# DMXController.net
KiCad netlist of a schematic drawn in Altium Designer
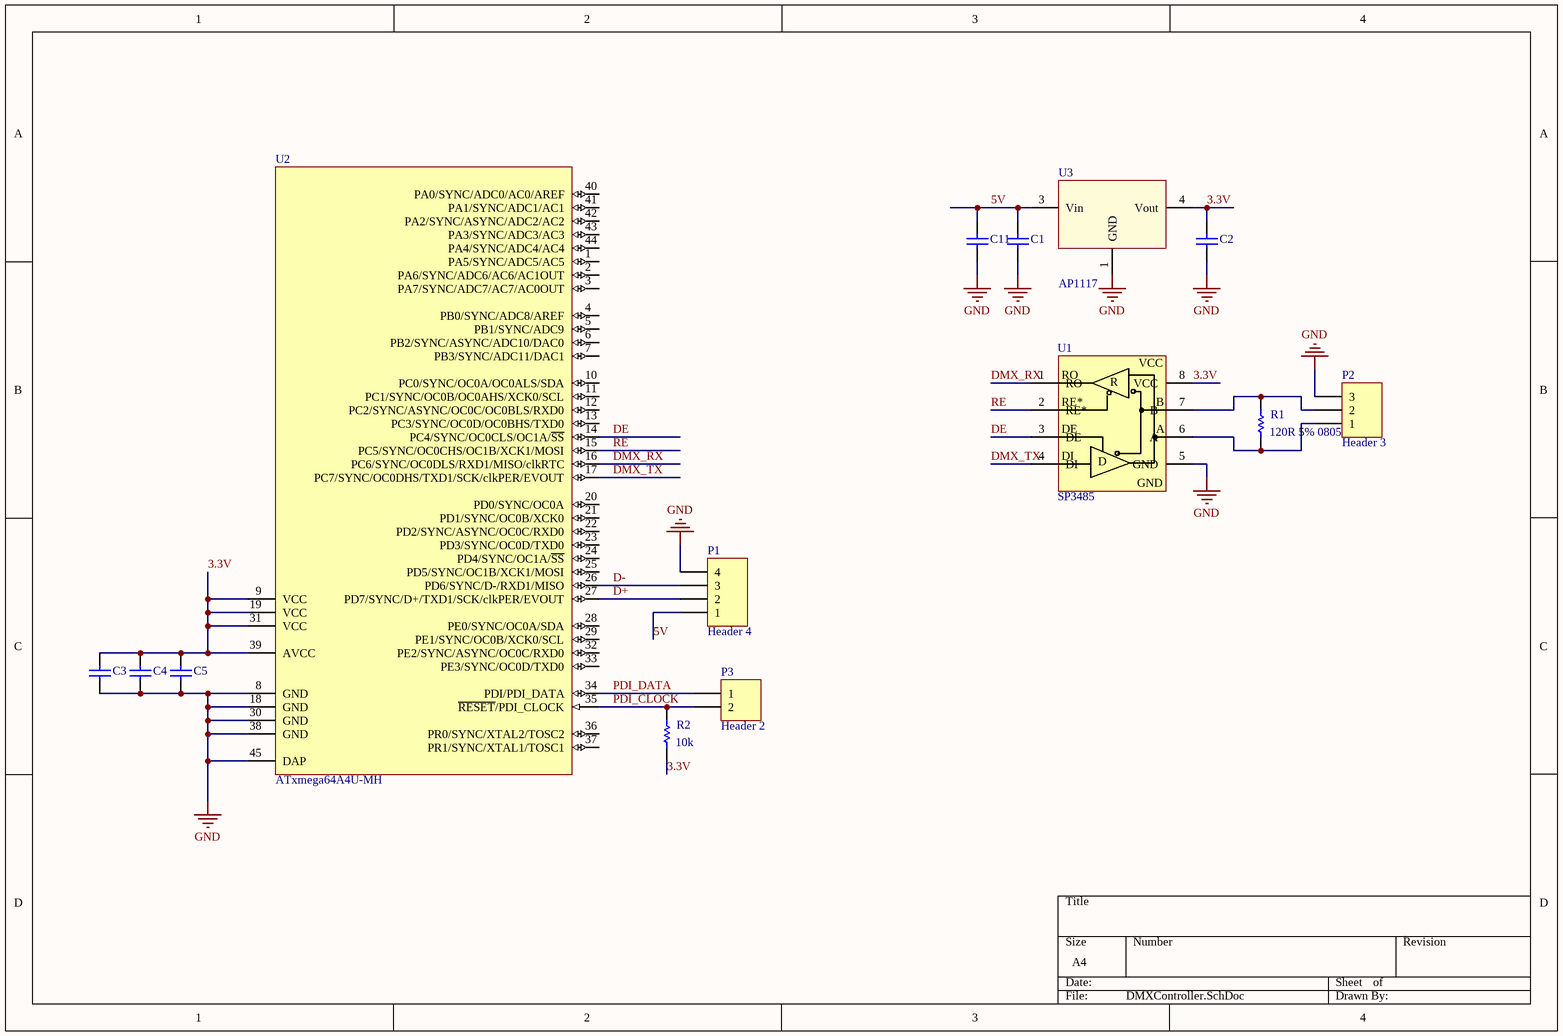
[diagram p0: DMXController.SchDoc]

(export (version "E")
  (design (tool "Eeschema 10.0.6"))
  (components
    (comp (ref "C1")
      (value "10u")
      (footprint "CAPC0805(2012)100_M")
      (description "CAP 1uF 10V ±10% 0805 (2012 Metric) Thickness 1mm SMD")
      (fields (field (name "TOLERANCE") "±10%"))
      (libsource (lib "Altium Content Vault") (part "CMP-1036-04739-1"))
    )
    (comp (ref "C2")
      (value "22u")
      (footprint "CAPC0805(2012)100_M")
      (description "CAP 1uF 10V ±10% 0805 (2012 Metric) Thickness 1mm SMD")
      (fields (field (name "TOLERANCE") "±10%"))
      (libsource (lib "Altium Content Vault") (part "CMP-1036-04739-1"))
    )
    (comp (ref "C3")
      (value "100n")
      (footprint "CAPC0805(2012)100_M")
      (description "CAP 1uF 10V ±10% 0805 (2012 Metric) Thickness 1mm SMD")
      (fields (field (name "TOLERANCE") "±10%"))
      (libsource (lib "Altium Content Vault") (part "CMP-1036-04739-1"))
    )
    (comp (ref "C4")
      (value "100n")
      (footprint "CAPC0805(2012)100_M")
      (description "CAP 1uF 10V ±10% 0805 (2012 Metric) Thickness 1mm SMD")
      (fields (field (name "TOLERANCE") "±10%"))
      (libsource (lib "Altium Content Vault") (part "CMP-1036-04739-1"))
    )
    (comp (ref "C5")
      (value "100n")
      (footprint "CAPC0805(2012)100_M")
      (description "CAP 1uF 10V ±10% 0805 (2012 Metric) Thickness 1mm SMD")
      (fields (field (name "TOLERANCE") "±10%"))
      (libsource (lib "Altium Content Vault") (part "CMP-1036-04739-1"))
    )
    (comp (ref "C11")
      (value "10u")
      (footprint "CAPC0805(2012)100_M")
      (description "CAP 1uF 10V ±10% 0805 (2012 Metric) Thickness 1mm SMD")
      (fields (field (name "TOLERANCE") "±10%"))
      (libsource (lib "Altium Content Vault") (part "CMP-1036-04739-1"))
    )
    (comp (ref "P1")
      (value "Header 4")
      (footprint "HDR1X4")
      (description "Header, 4-Pin")
      (fields (field (name "PUBLISHER") "Altium Limited"))
      (libsource (lib "Miscellaneous Connectors") (part "Header 4"))
    )
    (comp (ref "P2")
      (value "Header 3")
      (footprint "HDR1X3")
      (description "Header, 3-Pin")
      (fields (field (name "PUBLISHER") "Altium Limited"))
      (libsource (lib "Miscellaneous Connectors") (part "Header 3"))
    )
    (comp (ref "P3")
      (value "Header 2")
      (footprint "HDR1X2")
      (description "Header, 2-Pin")
      (fields (field (name "PUBLISHER") "Altium Limited"))
      (libsource (lib "Miscellaneous Connectors") (part "Header 2"))
    )
    (comp (ref "R1")
      (value "120R 5% 0805(2012)")
      (footprint "RESC0805(2012)_N")
      (description "120R 0.125W 5% 0805 (2012 Metric)  SMD")
      (fields (field (name "TOLERANCE") "5 %") (field (name "POWER") "0.125 W"))
      (libsource (lib "Altium Content Vault") (part "RES"))
    )
    (comp (ref "R2")
      (value "10k")
      (footprint "RESC0805(2012)_N")
      (description "120R 0.125W 5% 0805 (2012 Metric)  SMD")
      (fields (field (name "TOLERANCE") "5 %") (field (name "POWER") "0.125 W"))
      (libsource (lib "Altium Content Vault") (part "CMP-1013-00052-1"))
    )
    (comp (ref "U1") (value "SP3485") (footprint "SOIC8") (libsource (lib "Schlib1") (part "SP3485")))
    (comp (ref "U2")
      (value "ATxmega64A4U-MH")
      (footprint "44M1_L")
      (libsource (lib "Altium Content Vault") (part "MC-8B-ATXM16A4U-SQ45"))
    )
    (comp (ref "U3") (value "AP1117") (footprint "SOT-223") (libsource (lib "Schlib1") (part "AP1117")))
  )
  (nets
    (net (code "1") (name "/3.3V") (class "Default")
      (node (ref "C2") (pin "2") (pinfunction "2_2") (pintype "passive"))
      (node (ref "C3") (pin "2") (pinfunction "2_2") (pintype "passive"))
      (node (ref "C4") (pin "2") (pinfunction "2_2") (pintype "passive"))
      (node (ref "C5") (pin "2") (pinfunction "2_2") (pintype "passive"))
      (node (ref "R2") (pin "1") (pinfunction "1_1") (pintype "passive"))
      (node (ref "U1") (pin "8") (pinfunction "VCC_8") (pintype "passive"))
      (node (ref "U2") (pin "19") (pinfunction "VCC_19") (pintype "power_in"))
      (node (ref "U2") (pin "31") (pinfunction "VCC_31") (pintype "power_in"))
      (node (ref "U2") (pin "39") (pinfunction "AVCC_39") (pintype "power_in"))
      (node (ref "U2") (pin "9") (pinfunction "VCC_9") (pintype "power_in"))
      (node (ref "U3") (pin "4") (pinfunction "Vout_4") (pintype "passive"))
    )
    (net (code "2") (name "/5V") (class "Default")
      (node (ref "C1") (pin "2") (pinfunction "2_2") (pintype "passive"))
      (node (ref "C11") (pin "2") (pinfunction "2_2") (pintype "passive"))
      (node (ref "P1") (pin "1") (pinfunction "1_1") (pintype "passive"))
      (node (ref "U3") (pin "3") (pinfunction "Vin_3") (pintype "passive"))
    )
    (net (code "3") (name "/D+") (class "Default")
      (node (ref "P1") (pin "2") (pinfunction "2_2") (pintype "passive"))
      (node (ref "U2") (pin "27") (pinfunction "PD7/SYNC/D+/TXD1/SCK/clkPER/EVOUT_27") (pintype "bidirectional"))
    )
    (net (code "4") (name "/D-") (class "Default")
      (node (ref "P1") (pin "3") (pinfunction "3_3") (pintype "passive"))
      (node (ref "U2") (pin "26") (pinfunction "PD6/SYNC/D-/RXD1/MISO_26") (pintype "bidirectional"))
    )
    (net (code "5") (name "/DE") (class "Default")
      (node (ref "U1") (pin "3") (pinfunction "DE_3") (pintype "passive"))
      (node (ref "U2") (pin "14") (pinfunction "PC4/SYNC/OC0CLS/OC1A/~{SS}_14") (pintype "bidirectional"))
    )
    (net (code "6") (name "/DMX_RX") (class "Default")
      (node (ref "U1") (pin "1") (pinfunction "RO_1") (pintype "passive"))
      (node (ref "U2") (pin "16") (pinfunction "PC6/SYNC/OC0DLS/RXD1/MISO/clkRTC_16") (pintype "bidirectional"))
    )
    (net (code "7") (name "/DMX_TX") (class "Default")
      (node (ref "U1") (pin "4") (pinfunction "DI_4") (pintype "passive"))
      (node (ref "U2") (pin "17") (pinfunction "PC7/SYNC/OC0DHS/TXD1/SCK/clkPER/EVOUT_17") (pintype "bidirectional"))
    )
    (net (code "8") (name "/PDI_CLOCK") (class "Default")
      (node (ref "P3") (pin "2") (pinfunction "2_2") (pintype "passive"))
      (node (ref "R2") (pin "2") (pinfunction "2_2") (pintype "passive"))
      (node (ref "U2") (pin "35") (pinfunction "~{RESET}/PDI_CLOCK_35") (pintype "input"))
    )
    (net (code "9") (name "/PDI_DATA") (class "Default")
      (node (ref "P3") (pin "1") (pinfunction "1_1") (pintype "passive"))
      (node (ref "U2") (pin "34") (pinfunction "PDI/PDI_DATA_34") (pintype "bidirectional"))
    )
    (net (code "10") (name "/RE") (class "Default")
      (node (ref "U1") (pin "2") (pinfunction "RE*_2") (pintype "passive"))
      (node (ref "U2") (pin "15") (pinfunction "PC5/SYNC/OC0CHS/OC1B/XCK1/MOSI_15") (pintype "bidirectional"))
    )
    (net (code "11") (name "GND") (class "Default")
      (node (ref "C1") (pin "1") (pinfunction "1_1") (pintype "passive"))
      (node (ref "C11") (pin "1") (pinfunction "1_1") (pintype "passive"))
      (node (ref "C2") (pin "1") (pinfunction "1_1") (pintype "passive"))
      (node (ref "C3") (pin "1") (pinfunction "1_1") (pintype "passive"))
      (node (ref "C4") (pin "1") (pinfunction "1_1") (pintype "passive"))
      (node (ref "C5") (pin "1") (pinfunction "1_1") (pintype "passive"))
      (node (ref "P1") (pin "4") (pinfunction "4_4") (pintype "passive"))
      (node (ref "P2") (pin "3") (pinfunction "3_3") (pintype "passive"))
      (node (ref "U1") (pin "5") (pinfunction "GND_5") (pintype "passive"))
      (node (ref "U2") (pin "18") (pinfunction "GND_18") (pintype "power_in"))
      (node (ref "U2") (pin "30") (pinfunction "GND_30") (pintype "power_in"))
      (node (ref "U2") (pin "38") (pinfunction "GND_38") (pintype "power_in"))
      (node (ref "U2") (pin "45") (pinfunction "DAP_45") (pintype "power_in"))
      (node (ref "U2") (pin "8") (pinfunction "GND_8") (pintype "power_in"))
      (node (ref "U3") (pin "1") (pinfunction "GND_1") (pintype "passive"))
    )
    (net (code "12") (name "Net-(U1-A)") (class "Default")
      (node (ref "P2") (pin "1") (pinfunction "1_1") (pintype "passive"))
      (node (ref "R1") (pin "1") (pinfunction "1_1") (pintype "passive"))
      (node (ref "U1") (pin "6") (pinfunction "A_6") (pintype "passive"))
    )
    (net (code "13") (name "Net-(U1-B)") (class "Default")
      (node (ref "P2") (pin "2") (pinfunction "2_2") (pintype "passive"))
      (node (ref "R1") (pin "2") (pinfunction "2_2") (pintype "passive"))
      (node (ref "U1") (pin "7") (pinfunction "B_7") (pintype "passive"))
    )
    (net (code "14") (name "unconnected-(U2-PA0{slash}SYNC{slash}ADC0{slash}AC0{slash}AREF-Pad40)") (class "Default")
      (node (ref "U2") (pin "40") (pinfunction "PA0/SYNC/ADC0/AC0/AREF_40") (pintype "bidirectional"))
    )
    (net (code "15") (name "unconnected-(U2-PA1{slash}SYNC{slash}ADC1{slash}AC1-Pad41)") (class "Default")
      (node (ref "U2") (pin "41") (pinfunction "PA1/SYNC/ADC1/AC1_41") (pintype "bidirectional"))
    )
    (net (code "16") (name "unconnected-(U2-PA2{slash}SYNC{slash}ASYNC{slash}ADC2{slash}AC2-Pad42)") (class "Default")
      (node (ref "U2") (pin "42") (pinfunction "PA2/SYNC/ASYNC/ADC2/AC2_42") (pintype "bidirectional"))
    )
    (net (code "17") (name "unconnected-(U2-PA3{slash}SYNC{slash}ADC3{slash}AC3-Pad43)") (class "Default")
      (node (ref "U2") (pin "43") (pinfunction "PA3/SYNC/ADC3/AC3_43") (pintype "bidirectional"))
    )
    (net (code "18") (name "unconnected-(U2-PA4{slash}SYNC{slash}ADC4{slash}AC4-Pad44)") (class "Default")
      (node (ref "U2") (pin "44") (pinfunction "PA4/SYNC/ADC4/AC4_44") (pintype "bidirectional"))
    )
    (net (code "19") (name "unconnected-(U2-PA5{slash}SYNC{slash}ADC5{slash}AC5-Pad1)") (class "Default")
      (node (ref "U2") (pin "1") (pinfunction "PA5/SYNC/ADC5/AC5_1") (pintype "bidirectional"))
    )
    (net (code "20") (name "unconnected-(U2-PA6{slash}SYNC{slash}ADC6{slash}AC6{slash}AC1OUT-Pad2)") (class "Default")
      (node (ref "U2") (pin "2") (pinfunction "PA6/SYNC/ADC6/AC6/AC1OUT_2") (pintype "bidirectional"))
    )
    (net (code "21") (name "unconnected-(U2-PA7{slash}SYNC{slash}ADC7{slash}AC7{slash}AC0OUT-Pad3)") (class "Default")
      (node (ref "U2") (pin "3") (pinfunction "PA7/SYNC/ADC7/AC7/AC0OUT_3") (pintype "bidirectional"))
    )
    (net (code "22") (name "unconnected-(U2-PB0{slash}SYNC{slash}ADC8{slash}AREF-Pad4)") (class "Default")
      (node (ref "U2") (pin "4") (pinfunction "PB0/SYNC/ADC8/AREF_4") (pintype "bidirectional"))
    )
    (net (code "23") (name "unconnected-(U2-PB1{slash}SYNC{slash}ADC9-Pad5)") (class "Default")
      (node (ref "U2") (pin "5") (pinfunction "PB1/SYNC/ADC9_5") (pintype "bidirectional"))
    )
    (net (code "24") (name "unconnected-(U2-PB2{slash}SYNC{slash}ASYNC{slash}ADC10{slash}DAC0-Pad6)") (class "Default")
      (node (ref "U2") (pin "6") (pinfunction "PB2/SYNC/ASYNC/ADC10/DAC0_6") (pintype "bidirectional"))
    )
    (net (code "25") (name "unconnected-(U2-PB3{slash}SYNC{slash}ADC11{slash}DAC1-Pad7)") (class "Default")
      (node (ref "U2") (pin "7") (pinfunction "PB3/SYNC/ADC11/DAC1_7") (pintype "bidirectional"))
    )
    (net (code "26") (name "unconnected-(U2-PC0{slash}SYNC{slash}OC0A{slash}OC0ALS{slash}SDA-Pad10)") (class "Default")
      (node (ref "U2") (pin "10") (pinfunction "PC0/SYNC/OC0A/OC0ALS/SDA_10") (pintype "bidirectional"))
    )
    (net (code "27") (name "unconnected-(U2-PC1{slash}SYNC{slash}OC0B{slash}OC0AHS{slash}XCK0{slash}SCL-Pad11)") (class "Default")
      (node (ref "U2") (pin "11") (pinfunction "PC1/SYNC/OC0B/OC0AHS/XCK0/SCL_11") (pintype "bidirectional"))
    )
    (net (code "28") (name "unconnected-(U2-PC2{slash}SYNC{slash}ASYNC{slash}OC0C{slash}OC0BLS{slash}RXD0-Pad12)") (class "Default")
      (node (ref "U2") (pin "12") (pinfunction "PC2/SYNC/ASYNC/OC0C/OC0BLS/RXD0_12") (pintype "bidirectional"))
    )
    (net (code "29") (name "unconnected-(U2-PC3{slash}SYNC{slash}OC0D{slash}OC0BHS{slash}TXD0-Pad13)") (class "Default")
      (node (ref "U2") (pin "13") (pinfunction "PC3/SYNC/OC0D/OC0BHS/TXD0_13") (pintype "bidirectional"))
    )
    (net (code "30") (name "unconnected-(U2-PD0{slash}SYNC{slash}OC0A-Pad20)") (class "Default")
      (node (ref "U2") (pin "20") (pinfunction "PD0/SYNC/OC0A_20") (pintype "bidirectional"))
    )
    (net (code "31") (name "unconnected-(U2-PD1{slash}SYNC{slash}OC0B{slash}XCK0-Pad21)") (class "Default")
      (node (ref "U2") (pin "21") (pinfunction "PD1/SYNC/OC0B/XCK0_21") (pintype "bidirectional"))
    )
    (net (code "32") (name "unconnected-(U2-PD2{slash}SYNC{slash}ASYNC{slash}OC0C{slash}RXD0-Pad22)") (class "Default")
      (node (ref "U2") (pin "22") (pinfunction "PD2/SYNC/ASYNC/OC0C/RXD0_22") (pintype "bidirectional"))
    )
    (net (code "33") (name "unconnected-(U2-PD3{slash}SYNC{slash}OC0D{slash}TXD0-Pad23)") (class "Default")
      (node (ref "U2") (pin "23") (pinfunction "PD3/SYNC/OC0D/TXD0_23") (pintype "bidirectional"))
    )
    (net (code "34") (name "unconnected-(U2-PD4{slash}SYNC{slash}OC1A{slash}~{SS}-Pad24)") (class "Default")
      (node (ref "U2") (pin "24") (pinfunction "PD4/SYNC/OC1A/~{SS}_24") (pintype "bidirectional"))
    )
    (net (code "35") (name "unconnected-(U2-PD5{slash}SYNC{slash}OC1B{slash}XCK1{slash}MOSI-Pad25)") (class "Default")
      (node (ref "U2") (pin "25") (pinfunction "PD5/SYNC/OC1B/XCK1/MOSI_25") (pintype "bidirectional"))
    )
    (net (code "36") (name "unconnected-(U2-PE0{slash}SYNC{slash}OC0A{slash}SDA-Pad28)") (class "Default")
      (node (ref "U2") (pin "28") (pinfunction "PE0/SYNC/OC0A/SDA_28") (pintype "bidirectional"))
    )
    (net (code "37") (name "unconnected-(U2-PE1{slash}SYNC{slash}OC0B{slash}XCK0{slash}SCL-Pad29)") (class "Default")
      (node (ref "U2") (pin "29") (pinfunction "PE1/SYNC/OC0B/XCK0/SCL_29") (pintype "bidirectional"))
    )
    (net (code "38") (name "unconnected-(U2-PE2{slash}SYNC{slash}ASYNC{slash}OC0C{slash}RXD0-Pad32)") (class "Default")
      (node (ref "U2") (pin "32") (pinfunction "PE2/SYNC/ASYNC/OC0C/RXD0_32") (pintype "bidirectional"))
    )
    (net (code "39") (name "unconnected-(U2-PE3{slash}SYNC{slash}OC0D{slash}TXD0-Pad33)") (class "Default")
      (node (ref "U2") (pin "33") (pinfunction "PE3/SYNC/OC0D/TXD0_33") (pintype "bidirectional"))
    )
    (net (code "40") (name "unconnected-(U2-PR0{slash}SYNC{slash}XTAL2{slash}TOSC2-Pad36)") (class "Default")
      (node (ref "U2") (pin "36") (pinfunction "PR0/SYNC/XTAL2/TOSC2_36") (pintype "bidirectional"))
    )
    (net (code "41") (name "unconnected-(U2-PR1{slash}SYNC{slash}XTAL1{slash}TOSC1-Pad37)") (class "Default")
      (node (ref "U2") (pin "37") (pinfunction "PR1/SYNC/XTAL1/TOSC1_37") (pintype "bidirectional"))
    )
  )
)
